# M-Controller_REV-B.net
KiCad netlist of a schematic drawn in EAGLE
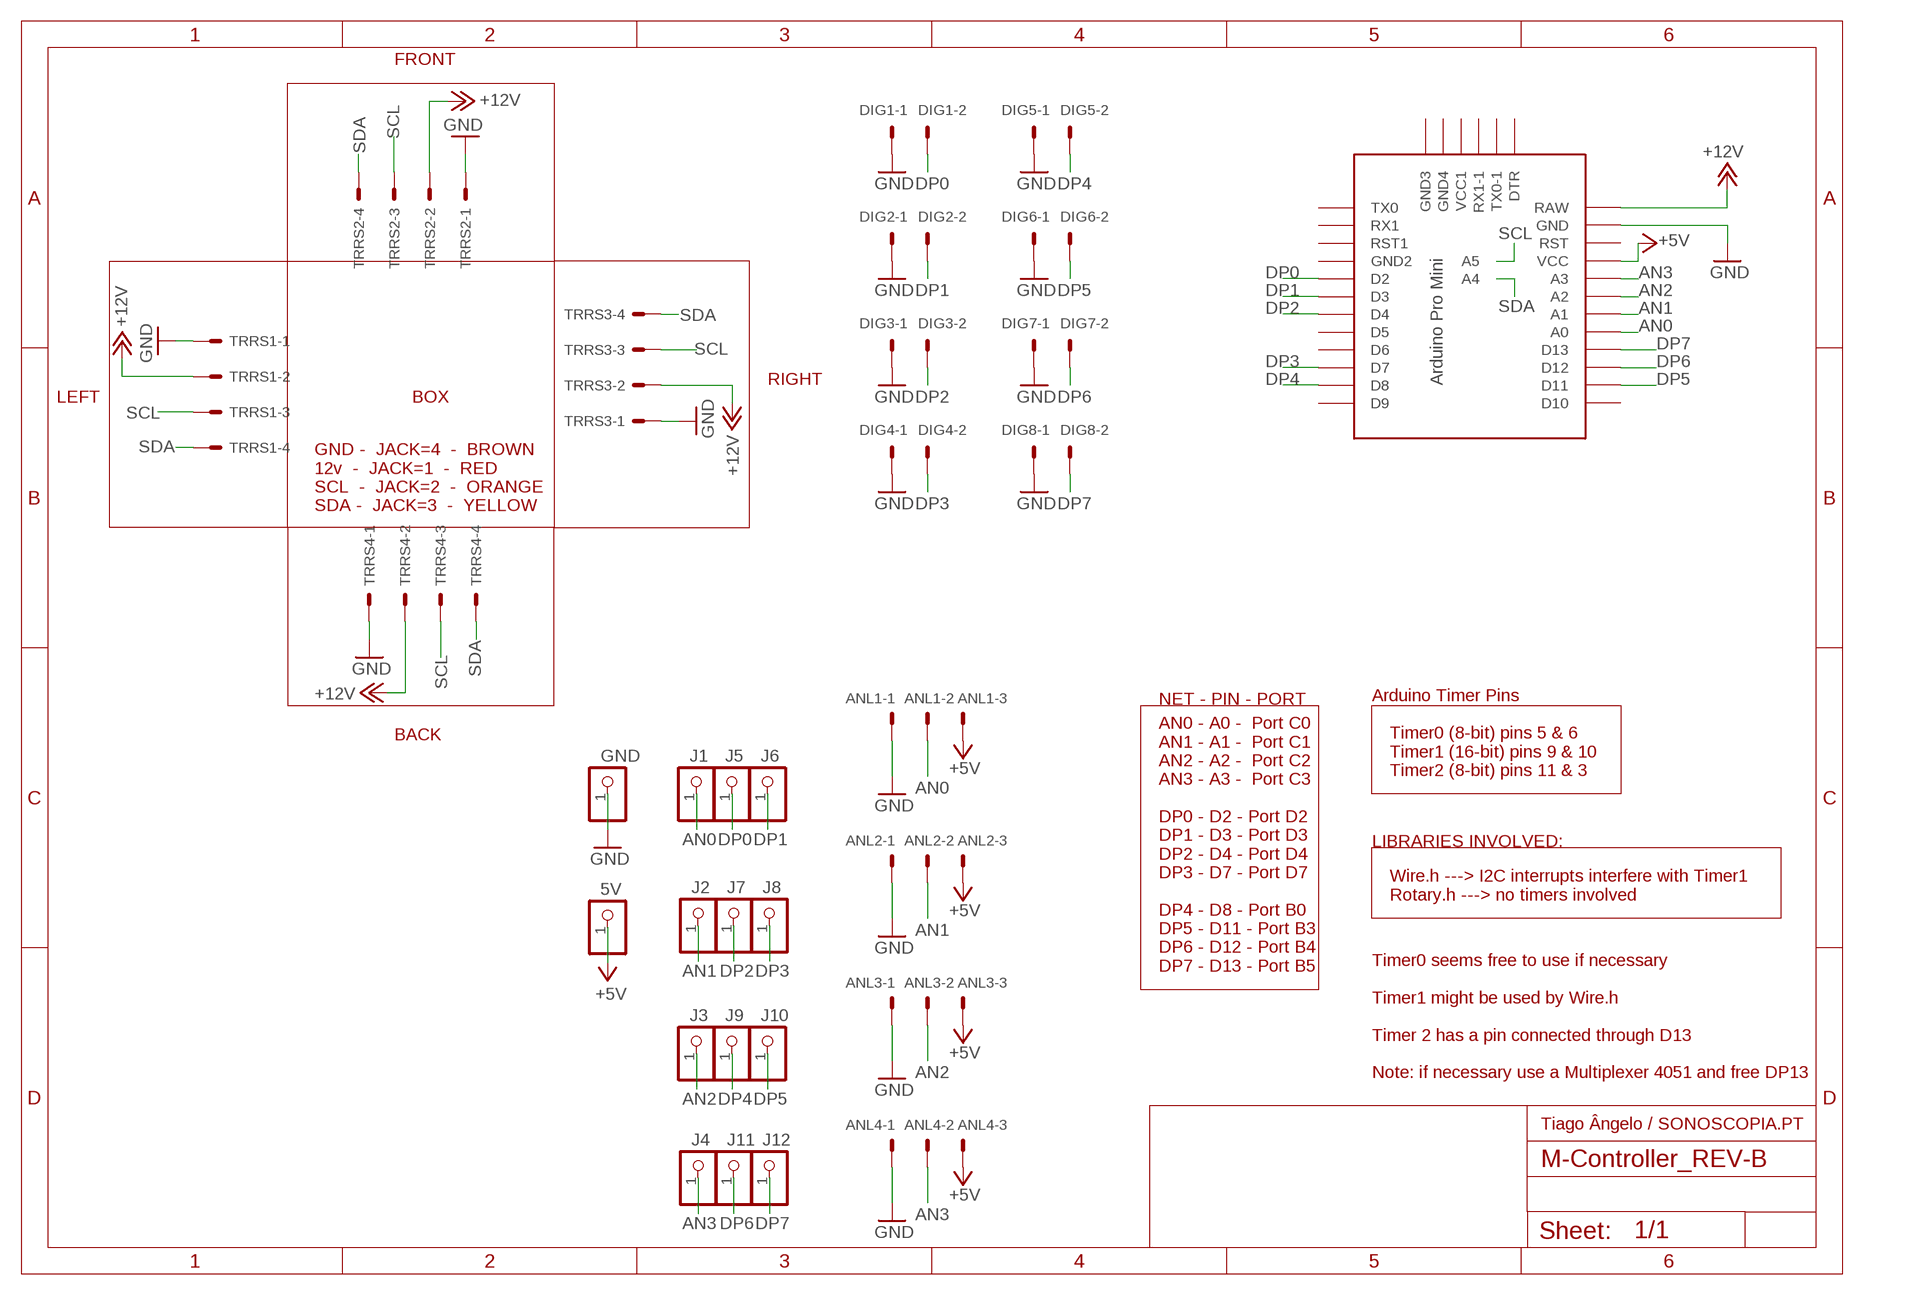
[diagram p0: schematic, sheet 1]

(export (version "E")
  (design (tool "Eeschema 10.0.6"))
  (components
    (comp (ref "5V")
      (value "PINHD-1X1")
      (footprint "eagle-import:1X01")
      (libsource (lib "eagle-import") (part "PINHD-1X1"))
    )
    (comp (ref "ANL1")
      (value "22-27-2031-03")
      (footprint "eagle-import:6410-03")
      (libsource (lib "eagle-import") (part "22-?-0327-2031"))
    )
    (comp (ref "ANL2")
      (value "22-27-2031-03")
      (footprint "eagle-import:6410-03")
      (libsource (lib "eagle-import") (part "22-?-0327-2031"))
    )
    (comp (ref "ANL3")
      (value "22-27-2031-03")
      (footprint "eagle-import:6410-03")
      (libsource (lib "eagle-import") (part "22-?-0327-2031"))
    )
    (comp (ref "ANL4")
      (value "22-27-2031-03")
      (footprint "eagle-import:6410-03")
      (libsource (lib "eagle-import") (part "22-?-0327-2031"))
    )
    (comp (ref "DIG1")
      (value "22-27-2021-02")
      (footprint "eagle-import:6410-02")
      (libsource (lib "eagle-import") (part "22-?-0227-2021"))
    )
    (comp (ref "DIG2")
      (value "22-27-2021-02")
      (footprint "eagle-import:6410-02")
      (libsource (lib "eagle-import") (part "22-?-0227-2021"))
    )
    (comp (ref "DIG3")
      (value "22-27-2021-02")
      (footprint "eagle-import:6410-02")
      (libsource (lib "eagle-import") (part "22-?-0227-2021"))
    )
    (comp (ref "DIG4")
      (value "22-27-2021-02")
      (footprint "eagle-import:6410-02")
      (libsource (lib "eagle-import") (part "22-?-0227-2021"))
    )
    (comp (ref "DIG5")
      (value "22-27-2021-02")
      (footprint "eagle-import:6410-02")
      (libsource (lib "eagle-import") (part "22-?-0227-2021"))
    )
    (comp (ref "DIG6")
      (value "22-27-2021-02")
      (footprint "eagle-import:6410-02")
      (libsource (lib "eagle-import") (part "22-?-0227-2021"))
    )
    (comp (ref "DIG7")
      (value "22-27-2021-02")
      (footprint "eagle-import:6410-02")
      (libsource (lib "eagle-import") (part "22-?-0227-2021"))
    )
    (comp (ref "DIG8")
      (value "22-27-2021-02")
      (footprint "eagle-import:6410-02")
      (libsource (lib "eagle-import") (part "22-?-0227-2021"))
    )
    (comp (ref "GND")
      (value "PINHD-1X1")
      (footprint "eagle-import:1X01")
      (libsource (lib "eagle-import") (part "PINHD-1X1"))
    )
    (comp (ref "J1")
      (value "PINHD-1X1")
      (footprint "eagle-import:1X01")
      (libsource (lib "eagle-import") (part "PINHD-1X1"))
    )
    (comp (ref "J2")
      (value "PINHD-1X1")
      (footprint "eagle-import:1X01")
      (libsource (lib "eagle-import") (part "PINHD-1X1"))
    )
    (comp (ref "J3")
      (value "PINHD-1X1")
      (footprint "eagle-import:1X01")
      (libsource (lib "eagle-import") (part "PINHD-1X1"))
    )
    (comp (ref "J4")
      (value "PINHD-1X1")
      (footprint "eagle-import:1X01")
      (libsource (lib "eagle-import") (part "PINHD-1X1"))
    )
    (comp (ref "J5")
      (value "PINHD-1X1")
      (footprint "eagle-import:1X01")
      (libsource (lib "eagle-import") (part "PINHD-1X1"))
    )
    (comp (ref "J6")
      (value "PINHD-1X1")
      (footprint "eagle-import:1X01")
      (libsource (lib "eagle-import") (part "PINHD-1X1"))
    )
    (comp (ref "J7")
      (value "PINHD-1X1")
      (footprint "eagle-import:1X01")
      (libsource (lib "eagle-import") (part "PINHD-1X1"))
    )
    (comp (ref "J8")
      (value "PINHD-1X1")
      (footprint "eagle-import:1X01")
      (libsource (lib "eagle-import") (part "PINHD-1X1"))
    )
    (comp (ref "J9")
      (value "PINHD-1X1")
      (footprint "eagle-import:1X01")
      (libsource (lib "eagle-import") (part "PINHD-1X1"))
    )
    (comp (ref "J10")
      (value "PINHD-1X1")
      (footprint "eagle-import:1X01")
      (libsource (lib "eagle-import") (part "PINHD-1X1"))
    )
    (comp (ref "J11")
      (value "PINHD-1X1")
      (footprint "eagle-import:1X01")
      (libsource (lib "eagle-import") (part "PINHD-1X1"))
    )
    (comp (ref "J12")
      (value "PINHD-1X1")
      (footprint "eagle-import:1X01")
      (libsource (lib "eagle-import") (part "PINHD-1X1"))
    )
    (comp (ref "TRRS1")
      (value "22-27-2041-04")
      (footprint "eagle-import:6410-04")
      (libsource (lib "eagle-import") (part "22-?-0427-2041"))
    )
    (comp (ref "TRRS2")
      (value "22-27-2041-04")
      (footprint "eagle-import:6410-04")
      (libsource (lib "eagle-import") (part "22-?-0427-2041"))
    )
    (comp (ref "TRRS3")
      (value "22-27-2041-04")
      (footprint "eagle-import:6410-04")
      (libsource (lib "eagle-import") (part "22-?-0427-2041"))
    )
    (comp (ref "TRRS4")
      (value "22-27-2041-04")
      (footprint "eagle-import:6410-04")
      (libsource (lib "eagle-import") (part "22-?-0427-2041"))
    )
    (comp (ref "U$1")
      (value "PRO-MINI-2")
      (footprint "eagle-import:PRO-MINI-2")
      (libsource (lib "eagle-import") (part "PRO-MINI-2"))
    )
  )
  (nets
    (net (code "1") (name "+5V") (class "Default")
      (node (ref "5V") (pin "1") (pinfunction "1_1") (pintype "passive"))
      (node (ref "ANL1") (pin "3") (pinfunction "S_3") (pintype "passive"))
      (node (ref "ANL2") (pin "3") (pinfunction "S_3") (pintype "passive"))
      (node (ref "ANL3") (pin "3") (pinfunction "S_3") (pintype "passive"))
      (node (ref "ANL4") (pin "3") (pinfunction "S_3") (pintype "passive"))
      (node (ref "U$1") (pin "VCC") (pinfunction "VCC_VCC") (pintype "bidirectional"))
    )
    (net (code "2") (name "+12V") (class "Default")
      (node (ref "TRRS1") (pin "2") (pinfunction "S_2") (pintype "passive"))
      (node (ref "TRRS2") (pin "2") (pinfunction "S_2") (pintype "passive"))
      (node (ref "TRRS3") (pin "2") (pinfunction "S_2") (pintype "passive"))
      (node (ref "TRRS4") (pin "2") (pinfunction "S_2") (pintype "passive"))
      (node (ref "U$1") (pin "RAW") (pinfunction "RAW_RAW") (pintype "bidirectional"))
    )
    (net (code "3") (name "/AN0") (class "Default")
      (node (ref "ANL1") (pin "2") (pinfunction "S_2") (pintype "passive"))
      (node (ref "J1") (pin "1") (pinfunction "1_1") (pintype "passive"))
      (node (ref "U$1") (pin "A0") (pinfunction "A0_A0") (pintype "bidirectional"))
    )
    (net (code "4") (name "/AN1") (class "Default")
      (node (ref "ANL2") (pin "2") (pinfunction "S_2") (pintype "passive"))
      (node (ref "J2") (pin "1") (pinfunction "1_1") (pintype "passive"))
      (node (ref "U$1") (pin "A1") (pinfunction "A1_A1") (pintype "bidirectional"))
    )
    (net (code "5") (name "/AN2") (class "Default")
      (node (ref "ANL3") (pin "2") (pinfunction "S_2") (pintype "passive"))
      (node (ref "J3") (pin "1") (pinfunction "1_1") (pintype "passive"))
      (node (ref "U$1") (pin "A2") (pinfunction "A2_A2") (pintype "bidirectional"))
    )
    (net (code "6") (name "/AN3") (class "Default")
      (node (ref "ANL4") (pin "2") (pinfunction "S_2") (pintype "passive"))
      (node (ref "J4") (pin "1") (pinfunction "1_1") (pintype "passive"))
      (node (ref "U$1") (pin "A3") (pinfunction "A3_A3") (pintype "bidirectional"))
    )
    (net (code "7") (name "/DP0") (class "Default")
      (node (ref "DIG1") (pin "2") (pinfunction "S_2") (pintype "passive"))
      (node (ref "J5") (pin "1") (pinfunction "1_1") (pintype "passive"))
      (node (ref "U$1") (pin "D2") (pinfunction "D2_D2") (pintype "bidirectional"))
    )
    (net (code "8") (name "/DP1") (class "Default")
      (node (ref "DIG2") (pin "2") (pinfunction "S_2") (pintype "passive"))
      (node (ref "J6") (pin "1") (pinfunction "1_1") (pintype "passive"))
      (node (ref "U$1") (pin "D3") (pinfunction "D3_D3") (pintype "bidirectional"))
    )
    (net (code "9") (name "/DP2") (class "Default")
      (node (ref "DIG3") (pin "2") (pinfunction "S_2") (pintype "passive"))
      (node (ref "J7") (pin "1") (pinfunction "1_1") (pintype "passive"))
      (node (ref "U$1") (pin "D4") (pinfunction "D4_D4") (pintype "bidirectional"))
    )
    (net (code "10") (name "/DP3") (class "Default")
      (node (ref "DIG4") (pin "2") (pinfunction "S_2") (pintype "passive"))
      (node (ref "J8") (pin "1") (pinfunction "1_1") (pintype "passive"))
      (node (ref "U$1") (pin "D7") (pinfunction "D7_D7") (pintype "bidirectional"))
    )
    (net (code "11") (name "/DP4") (class "Default")
      (node (ref "DIG5") (pin "2") (pinfunction "S_2") (pintype "passive"))
      (node (ref "J9") (pin "1") (pinfunction "1_1") (pintype "passive"))
      (node (ref "U$1") (pin "D8") (pinfunction "D8_D8") (pintype "bidirectional"))
    )
    (net (code "12") (name "/DP5") (class "Default")
      (node (ref "DIG6") (pin "2") (pinfunction "S_2") (pintype "passive"))
      (node (ref "J10") (pin "1") (pinfunction "1_1") (pintype "passive"))
      (node (ref "U$1") (pin "D11") (pinfunction "D11_D11") (pintype "bidirectional"))
    )
    (net (code "13") (name "/DP6") (class "Default")
      (node (ref "DIG7") (pin "2") (pinfunction "S_2") (pintype "passive"))
      (node (ref "J11") (pin "1") (pinfunction "1_1") (pintype "passive"))
      (node (ref "U$1") (pin "D12") (pinfunction "D12_D12") (pintype "bidirectional"))
    )
    (net (code "14") (name "/DP7") (class "Default")
      (node (ref "DIG8") (pin "2") (pinfunction "S_2") (pintype "passive"))
      (node (ref "J12") (pin "1") (pinfunction "1_1") (pintype "passive"))
      (node (ref "U$1") (pin "D13") (pinfunction "D13_D13") (pintype "bidirectional"))
    )
    (net (code "15") (name "/SCL") (class "Default")
      (node (ref "TRRS1") (pin "3") (pinfunction "S_3") (pintype "passive"))
      (node (ref "TRRS2") (pin "3") (pinfunction "S_3") (pintype "passive"))
      (node (ref "TRRS3") (pin "3") (pinfunction "S_3") (pintype "passive"))
      (node (ref "TRRS4") (pin "3") (pinfunction "S_3") (pintype "passive"))
      (node (ref "U$1") (pin "A5") (pinfunction "A5_A5") (pintype "bidirectional"))
    )
    (net (code "16") (name "/SDA") (class "Default")
      (node (ref "TRRS1") (pin "4") (pinfunction "S_4") (pintype "passive"))
      (node (ref "TRRS2") (pin "4") (pinfunction "S_4") (pintype "passive"))
      (node (ref "TRRS3") (pin "4") (pinfunction "S_4") (pintype "passive"))
      (node (ref "TRRS4") (pin "4") (pinfunction "S_4") (pintype "passive"))
      (node (ref "U$1") (pin "A4") (pinfunction "A4_A4") (pintype "bidirectional"))
    )
    (net (code "17") (name "GND") (class "Default")
      (node (ref "ANL1") (pin "1") (pinfunction "S_1") (pintype "passive"))
      (node (ref "ANL2") (pin "1") (pinfunction "S_1") (pintype "passive"))
      (node (ref "ANL3") (pin "1") (pinfunction "S_1") (pintype "passive"))
      (node (ref "ANL4") (pin "1") (pinfunction "S_1") (pintype "passive"))
      (node (ref "DIG1") (pin "1") (pinfunction "S_1") (pintype "passive"))
      (node (ref "DIG2") (pin "1") (pinfunction "S_1") (pintype "passive"))
      (node (ref "DIG3") (pin "1") (pinfunction "S_1") (pintype "passive"))
      (node (ref "DIG4") (pin "1") (pinfunction "S_1") (pintype "passive"))
      (node (ref "DIG5") (pin "1") (pinfunction "S_1") (pintype "passive"))
      (node (ref "DIG6") (pin "1") (pinfunction "S_1") (pintype "passive"))
      (node (ref "DIG7") (pin "1") (pinfunction "S_1") (pintype "passive"))
      (node (ref "DIG8") (pin "1") (pinfunction "S_1") (pintype "passive"))
      (node (ref "GND") (pin "1") (pinfunction "1_1") (pintype "passive"))
      (node (ref "TRRS1") (pin "1") (pinfunction "S_1") (pintype "passive"))
      (node (ref "TRRS2") (pin "1") (pinfunction "S_1") (pintype "passive"))
      (node (ref "TRRS3") (pin "1") (pinfunction "S_1") (pintype "passive"))
      (node (ref "TRRS4") (pin "1") (pinfunction "S_1") (pintype "passive"))
      (node (ref "U$1") (pin "GND") (pinfunction "GND_GND") (pintype "bidirectional"))
    )
    (net (code "18") (name "unconnected-(U$1-GND2-PadGND1)") (class "Default")
      (node (ref "U$1") (pin "GND1") (pinfunction "GND2_GND1") (pintype "bidirectional"))
    )
    (net (code "19") (name "unconnected-(U$1-GND3-PadGND2)") (class "Default")
      (node (ref "U$1") (pin "GND2") (pinfunction "GND3_GND2") (pintype "bidirectional"))
    )
    (net (code "20") (name "unconnected-(U$1-GND4-PadGND3)") (class "Default")
      (node (ref "U$1") (pin "GND3") (pinfunction "GND4_GND3") (pintype "bidirectional"))
    )
    (net (code "21") (name "unconnected-(U$1-PadD5)") (class "Default")
      (node (ref "U$1") (pin "D5") (pinfunction "D5_D5") (pintype "bidirectional"))
    )
    (net (code "22") (name "unconnected-(U$1-PadD6)") (class "Default")
      (node (ref "U$1") (pin "D6") (pinfunction "D6_D6") (pintype "bidirectional"))
    )
    (net (code "23") (name "unconnected-(U$1-PadD9)") (class "Default")
      (node (ref "U$1") (pin "D9") (pinfunction "D9_D9") (pintype "bidirectional"))
    )
    (net (code "24") (name "unconnected-(U$1-PadD10)") (class "Default")
      (node (ref "U$1") (pin "D10") (pinfunction "D10_D10") (pintype "bidirectional"))
    )
    (net (code "25") (name "unconnected-(U$1-PadDTR)") (class "Default")
      (node (ref "U$1") (pin "DTR") (pinfunction "DTR_DTR") (pintype "bidirectional"))
    )
    (net (code "26") (name "unconnected-(U$1-PadRST)") (class "Default")
      (node (ref "U$1") (pin "RST") (pinfunction "RST_RST") (pintype "bidirectional"))
    )
    (net (code "27") (name "unconnected-(U$1-PadRST1)") (class "Default")
      (node (ref "U$1") (pin "RST1") (pinfunction "RST1_RST1") (pintype "bidirectional"))
    )
    (net (code "28") (name "unconnected-(U$1-PadRX1)") (class "Default")
      (node (ref "U$1") (pin "RX1") (pinfunction "RX1_RX1") (pintype "bidirectional"))
    )
    (net (code "29") (name "unconnected-(U$1-PadRX1-1)") (class "Default")
      (node (ref "U$1") (pin "RX1-1") (pinfunction "RX1-1_RX1-1") (pintype "bidirectional"))
    )
    (net (code "30") (name "unconnected-(U$1-PadTX0)") (class "Default")
      (node (ref "U$1") (pin "TX0") (pinfunction "TX0_TX0") (pintype "bidirectional"))
    )
    (net (code "31") (name "unconnected-(U$1-PadTX0-1)") (class "Default")
      (node (ref "U$1") (pin "TX0-1") (pinfunction "TX0-1_TX0-1") (pintype "bidirectional"))
    )
    (net (code "32") (name "unconnected-(U$1-PadVCC1)") (class "Default")
      (node (ref "U$1") (pin "VCC1") (pinfunction "VCC1_VCC1") (pintype "bidirectional"))
    )
  )
)
